# teensy_amp_R3b.net
KiCad netlist of a schematic drawn in EAGLE
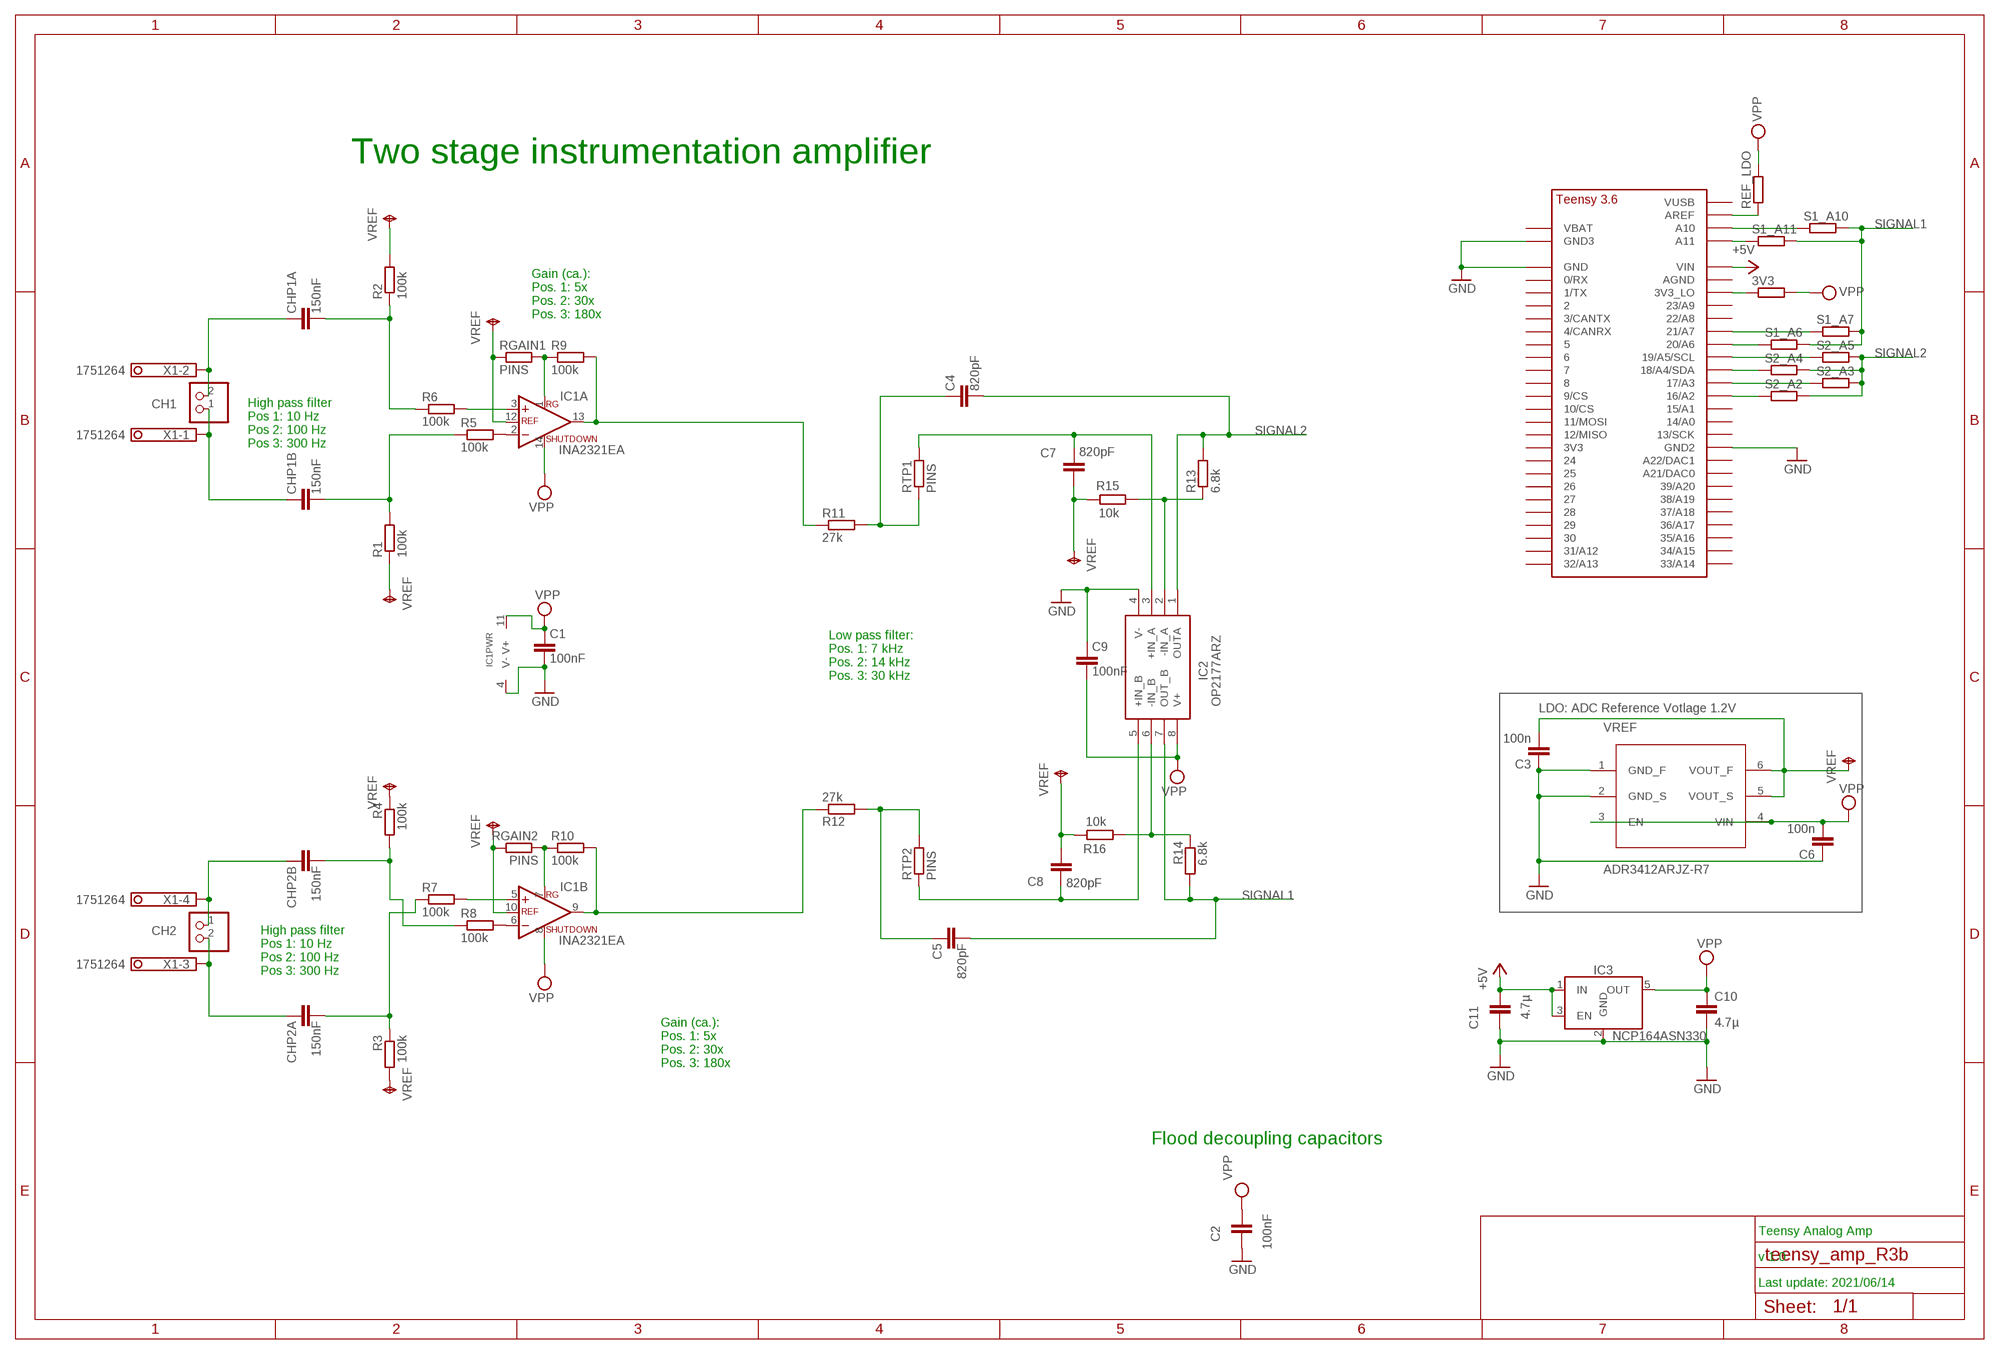
[diagram p0: schematic, sheet 1]

(export (version "E")
  (design (tool "Eeschema 10.0.6"))
  (components
    (comp (ref "3V3")
      (value "R_JLM0402-NARROW")
      (footprint "eagle-import:0402-N")
      (libsource (lib "eagle-import") (part "R_JLM0402-NARROW"))
    )
    (comp (ref "C1")
      (value "100nF")
      (footprint "eagle-import:C0603")
      (libsource (lib "eagle-import") (part "C-EUC0603"))
    )
    (comp (ref "C2")
      (value "100nF")
      (footprint "eagle-import:C0603")
      (libsource (lib "eagle-import") (part "C-EUC0603"))
    )
    (comp (ref "C3")
      (value "100n")
      (footprint "eagle-import:C0603")
      (libsource (lib "eagle-import") (part "C-EUC0603"))
    )
    (comp (ref "C4")
      (value "820pF")
      (footprint "eagle-import:C0603")
      (libsource (lib "eagle-import") (part "C-EUC0603"))
    )
    (comp (ref "C5")
      (value "820pF")
      (footprint "eagle-import:C0603")
      (libsource (lib "eagle-import") (part "C-EUC0603"))
    )
    (comp (ref "C6")
      (value "100n")
      (footprint "eagle-import:C0603")
      (libsource (lib "eagle-import") (part "C-EUC0603"))
    )
    (comp (ref "C7")
      (value "820pF")
      (footprint "eagle-import:C0603")
      (libsource (lib "eagle-import") (part "C-EUC0603"))
    )
    (comp (ref "C8")
      (value "820pF")
      (footprint "eagle-import:C0603")
      (libsource (lib "eagle-import") (part "C-EUC0603"))
    )
    (comp (ref "C9")
      (value "100nF")
      (footprint "eagle-import:C0603")
      (libsource (lib "eagle-import") (part "C-EUC0603"))
    )
    (comp (ref "C10")
      (value "4.7µ")
      (footprint "eagle-import:C0603")
      (libsource (lib "eagle-import") (part "C-EUC0603"))
    )
    (comp (ref "C11")
      (value "4.7µ")
      (footprint "eagle-import:C0603")
      (libsource (lib "eagle-import") (part "C-EUC0603"))
    )
    (comp (ref "CH1")
      (value "PINHD-1X2")
      (footprint "eagle-import:1X02")
      (libsource (lib "eagle-import") (part "PINHD-1X2"))
    )
    (comp (ref "CH2")
      (value "PINHD-1X2")
      (footprint "eagle-import:1X02")
      (libsource (lib "eagle-import") (part "PINHD-1X2"))
    )
    (comp (ref "CHP1A")
      (value "150nF")
      (footprint "eagle-import:C_PINS")
      (libsource (lib "eagle-import") (part "C-EUC_PINS"))
    )
    (comp (ref "CHP1B")
      (value "150nF")
      (footprint "eagle-import:C_PINS")
      (libsource (lib "eagle-import") (part "C-EUC_PINS"))
    )
    (comp (ref "CHP2A")
      (value "150nF")
      (footprint "eagle-import:C_PINS")
      (libsource (lib "eagle-import") (part "C-EUC_PINS"))
    )
    (comp (ref "CHP2B")
      (value "150nF")
      (footprint "eagle-import:C_PINS")
      (libsource (lib "eagle-import") (part "C-EUC_PINS"))
    )
    (comp (ref "IC1")
      (value "INA2321EA")
      (footprint "eagle-import:TSSOP14")
      (libsource (lib "eagle-import") (part "INA2321EA"))
    )
    (comp (ref "IC2")
      (value "OP2177ARZ")
      (footprint "eagle-import:SOIC127P600X175-8N")
      (fields (field (name "MOUSER_PART_NUMBER") "584-OP2177ARZ"))
      (libsource (lib "eagle-import") (part "OP2177ARZ"))
    )
    (comp (ref "IC3")
      (value "NCP164ASN330")
      (footprint "eagle-import:SOT23-5")
      (libsource (lib "eagle-import") (part "LDO_ENSOT23-5"))
    )
    (comp (ref "R1")
      (value "100k")
      (footprint "eagle-import:R0603")
      (libsource (lib "eagle-import") (part "R_JLMR0603"))
    )
    (comp (ref "R2")
      (value "100k")
      (footprint "eagle-import:R0603")
      (libsource (lib "eagle-import") (part "R_JLMR0603"))
    )
    (comp (ref "R3")
      (value "100k")
      (footprint "eagle-import:R0603")
      (libsource (lib "eagle-import") (part "R_JLMR0603"))
    )
    (comp (ref "R4")
      (value "100k")
      (footprint "eagle-import:R0603")
      (libsource (lib "eagle-import") (part "R_JLMR0603"))
    )
    (comp (ref "R5")
      (value "100k")
      (footprint "eagle-import:R0603")
      (libsource (lib "eagle-import") (part "R_JLMR0603"))
    )
    (comp (ref "R6")
      (value "100k")
      (footprint "eagle-import:R0603")
      (libsource (lib "eagle-import") (part "R_JLMR0603"))
    )
    (comp (ref "R7")
      (value "100k")
      (footprint "eagle-import:R0603")
      (libsource (lib "eagle-import") (part "R_JLMR0603"))
    )
    (comp (ref "R8")
      (value "100k")
      (footprint "eagle-import:R0603")
      (libsource (lib "eagle-import") (part "R_JLMR0603"))
    )
    (comp (ref "R9")
      (value "100k")
      (footprint "eagle-import:R0603")
      (libsource (lib "eagle-import") (part "R_JLMR0603"))
    )
    (comp (ref "R10")
      (value "100k")
      (footprint "eagle-import:R0603")
      (libsource (lib "eagle-import") (part "R_JLMR0603"))
    )
    (comp (ref "R11")
      (value "27k")
      (footprint "eagle-import:R0603")
      (libsource (lib "eagle-import") (part "R_JLMR0603"))
    )
    (comp (ref "R12")
      (value "27k")
      (footprint "eagle-import:R0603")
      (libsource (lib "eagle-import") (part "R_JLMR0603"))
    )
    (comp (ref "R13")
      (value "6.8k")
      (footprint "eagle-import:R0603")
      (libsource (lib "eagle-import") (part "R_JLMR0603"))
    )
    (comp (ref "R14")
      (value "6.8k")
      (footprint "eagle-import:R0603")
      (libsource (lib "eagle-import") (part "R_JLMR0603"))
    )
    (comp (ref "R15")
      (value "10k")
      (footprint "eagle-import:R0603")
      (libsource (lib "eagle-import") (part "R_JLMR0603"))
    )
    (comp (ref "R16")
      (value "10k")
      (footprint "eagle-import:R0603")
      (libsource (lib "eagle-import") (part "R_JLMR0603"))
    )
    (comp (ref "REF_LDO")
      (value "R_JLM0402-NARROW")
      (footprint "eagle-import:0402-N")
      (libsource (lib "eagle-import") (part "R_JLM0402-NARROW"))
    )
    (comp (ref "RGAIN1")
      (value "PINS")
      (footprint "eagle-import:R_PINS")
      (libsource (lib "eagle-import") (part "R_JLMPINS"))
    )
    (comp (ref "RGAIN2")
      (value "PINS")
      (footprint "eagle-import:R_PINS")
      (libsource (lib "eagle-import") (part "R_JLMPINS"))
    )
    (comp (ref "RTP1")
      (value "PINS")
      (footprint "eagle-import:R_PINS")
      (libsource (lib "eagle-import") (part "R_JLMPINS"))
    )
    (comp (ref "RTP2")
      (value "PINS")
      (footprint "eagle-import:R_PINS")
      (libsource (lib "eagle-import") (part "R_JLMPINS"))
    )
    (comp (ref "S1_A6")
      (value "R_JLM0402-NARROW")
      (footprint "eagle-import:0402-N")
      (libsource (lib "eagle-import") (part "R_JLM0402-NARROW"))
    )
    (comp (ref "S1_A7")
      (value "R_JLM0402-NARROW")
      (footprint "eagle-import:0402-N")
      (libsource (lib "eagle-import") (part "R_JLM0402-NARROW"))
    )
    (comp (ref "S1_A10")
      (value "R_JLM0402-NARROW")
      (footprint "eagle-import:0402-N")
      (libsource (lib "eagle-import") (part "R_JLM0402-NARROW"))
    )
    (comp (ref "S1_A11")
      (value "R_JLM0402-NARROW")
      (footprint "eagle-import:0402-N")
      (libsource (lib "eagle-import") (part "R_JLM0402-NARROW"))
    )
    (comp (ref "S2_A2")
      (value "R_JLM0402-NARROW")
      (footprint "eagle-import:0402-N")
      (libsource (lib "eagle-import") (part "R_JLM0402-NARROW"))
    )
    (comp (ref "S2_A3")
      (value "R_JLM0402-NARROW")
      (footprint "eagle-import:0402-N")
      (libsource (lib "eagle-import") (part "R_JLM0402-NARROW"))
    )
    (comp (ref "S2_A4")
      (value "R_JLM0402-NARROW")
      (footprint "eagle-import:0402-N")
      (libsource (lib "eagle-import") (part "R_JLM0402-NARROW"))
    )
    (comp (ref "S2_A5")
      (value "R_JLM0402-NARROW")
      (footprint "eagle-import:0402-N")
      (libsource (lib "eagle-import") (part "R_JLM0402-NARROW"))
    )
    (comp (ref "U$1")
      (value "TEENSY_3.5/3.6_SOCKET_VBAT")
      (footprint "eagle-import:TEENY_3.5_3.6_SOCKET_VBAT")
      (libsource (lib "eagle-import") (part "TEENSY_3.5/3.6_SOCKET_VBAT"))
    )
    (comp (ref "VREF")
      (value "ADR3412ARJZ-R7")
      (footprint "eagle-import:SOT23-6")
      (libsource (lib "eagle-import") (part "ADR3412ARJZ-R7"))
    )
    (comp (ref "X1")
      (value "1751264")
      (footprint "eagle-import:1751264")
      (libsource (lib "eagle-import") (part "1751264"))
    )
  )
  (nets
    (net (code "1") (name "+5V") (class "Default")
      (node (ref "C11") (pin "2") (pinfunction "2_2") (pintype "passive"))
      (node (ref "IC3") (pin "1") (pinfunction "IN_1") (pintype "input"))
      (node (ref "IC3") (pin "3") (pinfunction "EN_3") (pintype "input"))
      (node (ref "U$1") (pin "VIN") (pinfunction "VIN_VIN") (pintype "bidirectional"))
    )
    (net (code "2") (name "/SIGNAL1") (class "Default")
      (node (ref "C5") (pin "2") (pinfunction "2_2") (pintype "passive"))
      (node (ref "IC2") (pin "7") (pinfunction "OUT_B_7") (pintype "bidirectional"))
      (node (ref "R14") (pin "2") (pinfunction "2_2") (pintype "passive"))
      (node (ref "S1_A10") (pin "2") (pinfunction "2_2") (pintype "passive"))
      (node (ref "S1_A11") (pin "2") (pinfunction "2_2") (pintype "passive"))
      (node (ref "S1_A6") (pin "2") (pinfunction "2_2") (pintype "passive"))
      (node (ref "S1_A7") (pin "2") (pinfunction "2_2") (pintype "passive"))
    )
    (net (code "3") (name "/SIGNAL2") (class "Default")
      (node (ref "C4") (pin "2") (pinfunction "2_2") (pintype "passive"))
      (node (ref "IC2") (pin "1") (pinfunction "OUTA_1") (pintype "bidirectional"))
      (node (ref "R13") (pin "2") (pinfunction "2_2") (pintype "passive"))
      (node (ref "S2_A2") (pin "2") (pinfunction "2_2") (pintype "passive"))
      (node (ref "S2_A3") (pin "2") (pinfunction "2_2") (pintype "passive"))
      (node (ref "S2_A4") (pin "2") (pinfunction "2_2") (pintype "passive"))
      (node (ref "S2_A5") (pin "2") (pinfunction "2_2") (pintype "passive"))
    )
    (net (code "4") (name "GND") (class "Default")
      (node (ref "C1") (pin "2") (pinfunction "2_2") (pintype "passive"))
      (node (ref "C10") (pin "2") (pinfunction "2_2") (pintype "passive"))
      (node (ref "C11") (pin "1") (pinfunction "1_1") (pintype "passive"))
      (node (ref "C2") (pin "1") (pinfunction "1_1") (pintype "passive"))
      (node (ref "C3") (pin "1") (pinfunction "1_1") (pintype "passive"))
      (node (ref "C6") (pin "1") (pinfunction "1_1") (pintype "passive"))
      (node (ref "C9") (pin "1") (pinfunction "1_1") (pintype "passive"))
      (node (ref "IC1") (pin "4") (pinfunction "V-_4") (pintype "power_in"))
      (node (ref "IC2") (pin "4") (pinfunction "V-_4") (pintype "bidirectional"))
      (node (ref "IC3") (pin "2") (pinfunction "GND_2") (pintype "power_in"))
      (node (ref "U$1") (pin "GND") (pinfunction "GND_GND") (pintype "bidirectional"))
      (node (ref "U$1") (pin "GND2") (pinfunction "GND2_GND2") (pintype "bidirectional"))
      (node (ref "U$1") (pin "GND3") (pinfunction "GND3_GND3") (pintype "bidirectional"))
      (node (ref "VREF") (pin "1") (pinfunction "GND_F_1") (pintype "bidirectional"))
      (node (ref "VREF") (pin "2") (pinfunction "GND_S_2") (pintype "bidirectional"))
    )
    (net (code "5") (name "Net-(3V3-Pad1)") (class "Default")
      (node (ref "3V3") (pin "1") (pinfunction "1_1") (pintype "passive"))
      (node (ref "U$1") (pin "3V3_LO") (pinfunction "3V3_LO_3V3_LO") (pintype "bidirectional"))
    )
    (net (code "6") (name "Net-(C4-Pad1)") (class "Default")
      (node (ref "C4") (pin "1") (pinfunction "1_1") (pintype "passive"))
      (node (ref "R11") (pin "2") (pinfunction "2_2") (pintype "passive"))
      (node (ref "RTP1") (pin "1") (pinfunction "1_1") (pintype "passive"))
    )
    (net (code "7") (name "Net-(C5-Pad1)") (class "Default")
      (node (ref "C5") (pin "1") (pinfunction "1_1") (pintype "passive"))
      (node (ref "R12") (pin "2") (pinfunction "2_2") (pintype "passive"))
      (node (ref "RTP2") (pin "2") (pinfunction "2_2") (pintype "passive"))
    )
    (net (code "8") (name "Net-(CHP1A-Pad2)") (class "Default")
      (node (ref "CHP1A") (pin "2") (pinfunction "2_2") (pintype "passive"))
      (node (ref "R2") (pin "1") (pinfunction "1_1") (pintype "passive"))
      (node (ref "R6") (pin "1") (pinfunction "1_1") (pintype "passive"))
    )
    (net (code "9") (name "Net-(CHP1B-Pad2)") (class "Default")
      (node (ref "CHP1B") (pin "2") (pinfunction "2_2") (pintype "passive"))
      (node (ref "R1") (pin "2") (pinfunction "2_2") (pintype "passive"))
      (node (ref "R5") (pin "1") (pinfunction "1_1") (pintype "passive"))
    )
    (net (code "10") (name "Net-(CHP2A-Pad2)") (class "Default")
      (node (ref "CHP2A") (pin "2") (pinfunction "2_2") (pintype "passive"))
      (node (ref "R3") (pin "1") (pinfunction "1_1") (pintype "passive"))
      (node (ref "R7") (pin "1") (pinfunction "1_1") (pintype "passive"))
    )
    (net (code "11") (name "Net-(CHP2B-Pad2)") (class "Default")
      (node (ref "CHP2B") (pin "2") (pinfunction "2_2") (pintype "passive"))
      (node (ref "R4") (pin "2") (pinfunction "2_2") (pintype "passive"))
      (node (ref "R8") (pin "1") (pinfunction "1_1") (pintype "passive"))
    )
    (net (code "12") (name "Net-(IC1A-+IN)") (class "Default")
      (node (ref "IC1") (pin "3") (pinfunction "+IN_3") (pintype "input"))
      (node (ref "R6") (pin "2") (pinfunction "2_2") (pintype "passive"))
    )
    (net (code "13") (name "Net-(IC1A--IN)") (class "Default")
      (node (ref "IC1") (pin "2") (pinfunction "-IN_2") (pintype "input"))
      (node (ref "R5") (pin "2") (pinfunction "2_2") (pintype "passive"))
    )
    (net (code "14") (name "Net-(IC1A-OUT)") (class "Default")
      (node (ref "IC1") (pin "13") (pinfunction "OUT_13") (pintype "output"))
      (node (ref "R11") (pin "1") (pinfunction "1_1") (pintype "passive"))
      (node (ref "R9") (pin "2") (pinfunction "2_2") (pintype "passive"))
    )
    (net (code "15") (name "Net-(IC1A-RG)") (class "Default")
      (node (ref "IC1") (pin "1") (pinfunction "RG_1") (pintype "input"))
      (node (ref "R9") (pin "1") (pinfunction "1_1") (pintype "passive"))
      (node (ref "RGAIN1") (pin "2") (pinfunction "2_2") (pintype "passive"))
    )
    (net (code "16") (name "Net-(IC1B-+IN)") (class "Default")
      (node (ref "IC1") (pin "5") (pinfunction "+IN_5") (pintype "input"))
      (node (ref "R7") (pin "2") (pinfunction "2_2") (pintype "passive"))
    )
    (net (code "17") (name "Net-(IC1B--IN)") (class "Default")
      (node (ref "IC1") (pin "6") (pinfunction "-IN_6") (pintype "input"))
      (node (ref "R8") (pin "2") (pinfunction "2_2") (pintype "passive"))
    )
    (net (code "18") (name "Net-(IC1B-OUT)") (class "Default")
      (node (ref "IC1") (pin "9") (pinfunction "OUT_9") (pintype "output"))
      (node (ref "R10") (pin "2") (pinfunction "2_2") (pintype "passive"))
      (node (ref "R12") (pin "1") (pinfunction "1_1") (pintype "passive"))
    )
    (net (code "19") (name "Net-(IC1B-RG)") (class "Default")
      (node (ref "IC1") (pin "7") (pinfunction "RG_7") (pintype "input"))
      (node (ref "R10") (pin "1") (pinfunction "1_1") (pintype "passive"))
      (node (ref "RGAIN2") (pin "1") (pinfunction "1_1") (pintype "passive"))
    )
    (net (code "20") (name "Net-(IC2-+IN_A)") (class "Default")
      (node (ref "C7") (pin "1") (pinfunction "1_1") (pintype "passive"))
      (node (ref "IC2") (pin "3") (pinfunction "+IN_A_3") (pintype "bidirectional"))
      (node (ref "RTP1") (pin "2") (pinfunction "2_2") (pintype "passive"))
    )
    (net (code "21") (name "Net-(IC2-+IN_B)") (class "Default")
      (node (ref "C8") (pin "1") (pinfunction "1_1") (pintype "passive"))
      (node (ref "IC2") (pin "5") (pinfunction "+IN_B_5") (pintype "bidirectional"))
      (node (ref "RTP2") (pin "1") (pinfunction "1_1") (pintype "passive"))
    )
    (net (code "22") (name "Net-(IC2--IN_A)") (class "Default")
      (node (ref "IC2") (pin "2") (pinfunction "-IN_A_2") (pintype "bidirectional"))
      (node (ref "R13") (pin "1") (pinfunction "1_1") (pintype "passive"))
      (node (ref "R15") (pin "1") (pinfunction "1_1") (pintype "passive"))
    )
    (net (code "23") (name "Net-(IC2--IN_B)") (class "Default")
      (node (ref "IC2") (pin "6") (pinfunction "-IN_B_6") (pintype "bidirectional"))
      (node (ref "R14") (pin "1") (pinfunction "1_1") (pintype "passive"))
      (node (ref "R16") (pin "1") (pinfunction "1_1") (pintype "passive"))
    )
    (net (code "24") (name "Net-(REF_LDO-Pad1)") (class "Default")
      (node (ref "REF_LDO") (pin "1") (pinfunction "1_1") (pintype "passive"))
      (node (ref "U$1") (pin "AREF") (pinfunction "AREF_AREF") (pintype "bidirectional"))
    )
    (net (code "25") (name "Net-(S1_A6-Pad1)") (class "Default")
      (node (ref "S1_A6") (pin "1") (pinfunction "1_1") (pintype "passive"))
      (node (ref "U$1") (pin "20/A6") (pinfunction "20/A6_20/A6") (pintype "bidirectional"))
    )
    (net (code "26") (name "Net-(S1_A7-Pad1)") (class "Default")
      (node (ref "S1_A7") (pin "1") (pinfunction "1_1") (pintype "passive"))
      (node (ref "U$1") (pin "21/A7") (pinfunction "21/A7_21/A7") (pintype "bidirectional"))
    )
    (net (code "27") (name "Net-(S1_A10-Pad1)") (class "Default")
      (node (ref "S1_A10") (pin "1") (pinfunction "1_1") (pintype "passive"))
      (node (ref "U$1") (pin "A10") (pinfunction "A10_A10") (pintype "bidirectional"))
    )
    (net (code "28") (name "Net-(S1_A11-Pad1)") (class "Default")
      (node (ref "S1_A11") (pin "1") (pinfunction "1_1") (pintype "passive"))
      (node (ref "U$1") (pin "A11") (pinfunction "A11_A11") (pintype "bidirectional"))
    )
    (net (code "29") (name "Net-(S2_A2-Pad1)") (class "Default")
      (node (ref "S2_A2") (pin "1") (pinfunction "1_1") (pintype "passive"))
      (node (ref "U$1") (pin "16/A2") (pinfunction "16/A2_16/A2") (pintype "bidirectional"))
    )
    (net (code "30") (name "Net-(S2_A3-Pad1)") (class "Default")
      (node (ref "S2_A3") (pin "1") (pinfunction "1_1") (pintype "passive"))
      (node (ref "U$1") (pin "17/A3") (pinfunction "17/A3_17/A3") (pintype "bidirectional"))
    )
    (net (code "31") (name "Net-(S2_A4-Pad1)") (class "Default")
      (node (ref "S2_A4") (pin "1") (pinfunction "1_1") (pintype "passive"))
      (node (ref "U$1") (pin "18/A4/SDA") (pinfunction "18/A4/SDA_18/A4/SDA") (pintype "bidirectional"))
    )
    (net (code "32") (name "Net-(S2_A5-Pad1)") (class "Default")
      (node (ref "S2_A5") (pin "1") (pinfunction "1_1") (pintype "passive"))
      (node (ref "U$1") (pin "19/A5/SCL") (pinfunction "19/A5/SCL_19/A5/SCL") (pintype "bidirectional"))
    )
    (net (code "33") (name "Net-(X1A-K)") (class "Default")
      (node (ref "CH1") (pin "1") (pinfunction "1_1") (pintype "passive"))
      (node (ref "CHP1B") (pin "1") (pinfunction "1_1") (pintype "passive"))
      (node (ref "X1") (pin "1") (pinfunction "K_1") (pintype "passive"))
    )
    (net (code "34") (name "Net-(X1B-K)") (class "Default")
      (node (ref "CH1") (pin "2") (pinfunction "2_2") (pintype "passive"))
      (node (ref "CHP1A") (pin "1") (pinfunction "1_1") (pintype "passive"))
      (node (ref "X1") (pin "2") (pinfunction "K_2") (pintype "passive"))
    )
    (net (code "35") (name "Net-(X1C-K)") (class "Default")
      (node (ref "CH2") (pin "2") (pinfunction "2_2") (pintype "passive"))
      (node (ref "CHP2A") (pin "1") (pinfunction "1_1") (pintype "passive"))
      (node (ref "X1") (pin "3") (pinfunction "K_3") (pintype "passive"))
    )
    (net (code "36") (name "Net-(X1D-K)") (class "Default")
      (node (ref "CH2") (pin "1") (pinfunction "1_1") (pintype "passive"))
      (node (ref "CHP2B") (pin "1") (pinfunction "1_1") (pintype "passive"))
      (node (ref "X1") (pin "4") (pinfunction "K_4") (pintype "passive"))
    )
    (net (code "37") (name "VPP") (class "Default")
      (node (ref "3V3") (pin "2") (pinfunction "2_2") (pintype "passive"))
      (node (ref "C1") (pin "1") (pinfunction "1_1") (pintype "passive"))
      (node (ref "C10") (pin "1") (pinfunction "1_1") (pintype "passive"))
      (node (ref "C2") (pin "2") (pinfunction "2_2") (pintype "passive"))
      (node (ref "C6") (pin "2") (pinfunction "2_2") (pintype "passive"))
      (node (ref "C9") (pin "2") (pinfunction "2_2") (pintype "passive"))
      (node (ref "IC1") (pin "11") (pinfunction "V+_11") (pintype "power_in"))
      (node (ref "IC1") (pin "14") (pinfunction "SHUTDOWN_14") (pintype "input"))
      (node (ref "IC1") (pin "8") (pinfunction "SHUTDOWN_8") (pintype "input"))
      (node (ref "IC2") (pin "8") (pinfunction "V+_8") (pintype "bidirectional"))
      (node (ref "IC3") (pin "5") (pinfunction "OUT_5") (pintype "output"))
      (node (ref "REF_LDO") (pin "2") (pinfunction "2_2") (pintype "passive"))
      (node (ref "VREF") (pin "3") (pinfunction "EN_3") (pintype "bidirectional"))
      (node (ref "VREF") (pin "4") (pinfunction "VIN_4") (pintype "bidirectional"))
    )
    (net (code "38") (name "VREF") (class "Default")
      (node (ref "C3") (pin "2") (pinfunction "2_2") (pintype "passive"))
      (node (ref "C7") (pin "2") (pinfunction "2_2") (pintype "passive"))
      (node (ref "C8") (pin "2") (pinfunction "2_2") (pintype "passive"))
      (node (ref "IC1") (pin "10") (pinfunction "REF_10") (pintype "input"))
      (node (ref "IC1") (pin "12") (pinfunction "REF_12") (pintype "input"))
      (node (ref "R1") (pin "1") (pinfunction "1_1") (pintype "passive"))
      (node (ref "R15") (pin "2") (pinfunction "2_2") (pintype "passive"))
      (node (ref "R16") (pin "2") (pinfunction "2_2") (pintype "passive"))
      (node (ref "R2") (pin "2") (pinfunction "2_2") (pintype "passive"))
      (node (ref "R3") (pin "2") (pinfunction "2_2") (pintype "passive"))
      (node (ref "R4") (pin "1") (pinfunction "1_1") (pintype "passive"))
      (node (ref "RGAIN1") (pin "1") (pinfunction "1_1") (pintype "passive"))
      (node (ref "RGAIN2") (pin "2") (pinfunction "2_2") (pintype "passive"))
      (node (ref "VREF") (pin "5") (pinfunction "VOUT_S_5") (pintype "bidirectional"))
      (node (ref "VREF") (pin "6") (pinfunction "VOUT_F_6") (pintype "bidirectional"))
    )
    (net (code "39") (name "unconnected-(U$1-A21{slash}DAC0-Pad21{slash}DAC0)") (class "Default")
      (node (ref "U$1") (pin "21/DAC0") (pinfunction "A21/DAC0_21/DAC0") (pintype "bidirectional"))
    )
    (net (code "40") (name "unconnected-(U$1-Pad0{slash}RX)") (class "Default")
      (node (ref "U$1") (pin "0/RX") (pinfunction "0/RX_0/RX") (pintype "bidirectional"))
    )
    (net (code "41") (name "unconnected-(U$1-Pad1{slash}TX)") (class "Default")
      (node (ref "U$1") (pin "1/TX") (pinfunction "1/TX_1/TX") (pintype "bidirectional"))
    )
    (net (code "42") (name "unconnected-(U$1-Pad2)") (class "Default")
      (node (ref "U$1") (pin "2") (pinfunction "2_2") (pintype "bidirectional"))
    )
    (net (code "43") (name "unconnected-(U$1-Pad3V3)") (class "Default")
      (node (ref "U$1") (pin "3V3") (pinfunction "3V3_3V3") (pintype "bidirectional"))
    )
    (net (code "44") (name "unconnected-(U$1-Pad3{slash}CANTX)") (class "Default")
      (node (ref "U$1") (pin "3/CANTX") (pinfunction "3/CANTX_3/CANTX") (pintype "bidirectional"))
    )
    (net (code "45") (name "unconnected-(U$1-Pad4{slash}CANRX)") (class "Default")
      (node (ref "U$1") (pin "4/CANRX") (pinfunction "4/CANRX_4/CANRX") (pintype "bidirectional"))
    )
    (net (code "46") (name "unconnected-(U$1-Pad5)") (class "Default")
      (node (ref "U$1") (pin "5") (pinfunction "5_5") (pintype "bidirectional"))
    )
    (net (code "47") (name "unconnected-(U$1-Pad6)") (class "Default")
      (node (ref "U$1") (pin "6") (pinfunction "6_6") (pintype "bidirectional"))
    )
    (net (code "48") (name "unconnected-(U$1-Pad7)") (class "Default")
      (node (ref "U$1") (pin "7") (pinfunction "7_7") (pintype "bidirectional"))
    )
    (net (code "49") (name "unconnected-(U$1-Pad8)") (class "Default")
      (node (ref "U$1") (pin "8") (pinfunction "8_8") (pintype "bidirectional"))
    )
    (net (code "50") (name "unconnected-(U$1-Pad9{slash}CS)") (class "Default")
      (node (ref "U$1") (pin "9/CS") (pinfunction "9/CS_9/CS") (pintype "bidirectional"))
    )
    (net (code "51") (name "unconnected-(U$1-Pad10{slash}CS)") (class "Default")
      (node (ref "U$1") (pin "10/CS") (pinfunction "10/CS_10/CS") (pintype "bidirectional"))
    )
    (net (code "52") (name "unconnected-(U$1-Pad11{slash}MOSI)") (class "Default")
      (node (ref "U$1") (pin "11/MOSI") (pinfunction "11/MOSI_11/MOSI") (pintype "bidirectional"))
    )
    (net (code "53") (name "unconnected-(U$1-Pad12{slash}MISO)") (class "Default")
      (node (ref "U$1") (pin "12/MISO") (pinfunction "12/MISO_12/MISO") (pintype "bidirectional"))
    )
    (net (code "54") (name "unconnected-(U$1-Pad13{slash}SCK)") (class "Default")
      (node (ref "U$1") (pin "13/SCK") (pinfunction "13/SCK_13/SCK") (pintype "bidirectional"))
    )
    (net (code "55") (name "unconnected-(U$1-Pad14{slash}A0)") (class "Default")
      (node (ref "U$1") (pin "14/A0") (pinfunction "14/A0_14/A0") (pintype "bidirectional"))
    )
    (net (code "56") (name "unconnected-(U$1-Pad15{slash}A1)") (class "Default")
      (node (ref "U$1") (pin "15/A1") (pinfunction "15/A1_15/A1") (pintype "bidirectional"))
    )
    (net (code "57") (name "unconnected-(U$1-Pad22{slash}A8)") (class "Default")
      (node (ref "U$1") (pin "22/A8") (pinfunction "22/A8_22/A8") (pintype "bidirectional"))
    )
    (net (code "58") (name "unconnected-(U$1-Pad23{slash}A9)") (class "Default")
      (node (ref "U$1") (pin "23/A9") (pinfunction "23/A9_23/A9") (pintype "bidirectional"))
    )
    (net (code "59") (name "unconnected-(U$1-Pad24)") (class "Default")
      (node (ref "U$1") (pin "24") (pinfunction "24_24") (pintype "bidirectional"))
    )
    (net (code "60") (name "unconnected-(U$1-Pad25)") (class "Default")
      (node (ref "U$1") (pin "25") (pinfunction "25_25") (pintype "bidirectional"))
    )
    (net (code "61") (name "unconnected-(U$1-Pad26)") (class "Default")
      (node (ref "U$1") (pin "26") (pinfunction "26_26") (pintype "bidirectional"))
    )
    (net (code "62") (name "unconnected-(U$1-Pad27)") (class "Default")
      (node (ref "U$1") (pin "27") (pinfunction "27_27") (pintype "bidirectional"))
    )
    (net (code "63") (name "unconnected-(U$1-Pad28)") (class "Default")
      (node (ref "U$1") (pin "28") (pinfunction "28_28") (pintype "bidirectional"))
    )
    (net (code "64") (name "unconnected-(U$1-Pad29)") (class "Default")
      (node (ref "U$1") (pin "29") (pinfunction "29_29") (pintype "bidirectional"))
    )
    (net (code "65") (name "unconnected-(U$1-Pad30)") (class "Default")
      (node (ref "U$1") (pin "30") (pinfunction "30_30") (pintype "bidirectional"))
    )
    (net (code "66") (name "unconnected-(U$1-Pad31{slash}A12)") (class "Default")
      (node (ref "U$1") (pin "31/A12") (pinfunction "31/A12_31/A12") (pintype "bidirectional"))
    )
    (net (code "67") (name "unconnected-(U$1-Pad32{slash}A13)") (class "Default")
      (node (ref "U$1") (pin "32/A13") (pinfunction "32/A13_32/A13") (pintype "bidirectional"))
    )
    (net (code "68") (name "unconnected-(U$1-Pad33{slash}A14)") (class "Default")
      (node (ref "U$1") (pin "33/A14") (pinfunction "33/A14_33/A14") (pintype "bidirectional"))
    )
    (net (code "69") (name "unconnected-(U$1-Pad34{slash}A15)") (class "Default")
      (node (ref "U$1") (pin "34/A15") (pinfunction "34/A15_34/A15") (pintype "bidirectional"))
    )
    (net (code "70") (name "unconnected-(U$1-Pad35{slash}A16)") (class "Default")
      (node (ref "U$1") (pin "35/A16") (pinfunction "35/A16_35/A16") (pintype "bidirectional"))
    )
    (net (code "71") (name "unconnected-(U$1-Pad36{slash}A17)") (class "Default")
      (node (ref "U$1") (pin "36/A17") (pinfunction "36/A17_36/A17") (pintype "bidirectional"))
    )
    (net (code "72") (name "unconnected-(U$1-Pad37{slash}A18)") (class "Default")
      (node (ref "U$1") (pin "37/A18") (pinfunction "37/A18_37/A18") (pintype "bidirectional"))
    )
    (net (code "73") (name "unconnected-(U$1-Pad38{slash}A19)") (class "Default")
      (node (ref "U$1") (pin "38/A19") (pinfunction "38/A19_38/A19") (pintype "bidirectional"))
    )
    (net (code "74") (name "unconnected-(U$1-Pad39{slash}A20)") (class "Default")
      (node (ref "U$1") (pin "39/A20") (pinfunction "39/A20_39/A20") (pintype "bidirectional"))
    )
    (net (code "75") (name "unconnected-(U$1-PadA22{slash}DAC1)") (class "Default")
      (node (ref "U$1") (pin "A22/DAC1") (pinfunction "A22/DAC1_A22/DAC1") (pintype "bidirectional"))
    )
    (net (code "76") (name "unconnected-(U$1-PadAGND)") (class "Default")
      (node (ref "U$1") (pin "AGND") (pinfunction "AGND_AGND") (pintype "bidirectional"))
    )
    (net (code "77") (name "unconnected-(U$1-PadVBAT)") (class "Default")
      (node (ref "U$1") (pin "VBAT") (pinfunction "VBAT_VBAT") (pintype "bidirectional"))
    )
    (net (code "78") (name "unconnected-(U$1-PadVUSB)") (class "Default")
      (node (ref "U$1") (pin "VUSB") (pinfunction "VUSB_VUSB") (pintype "bidirectional"))
    )
  )
)
